# 32u4AVR.net
KiCad netlist of a schematic drawn in EAGLE
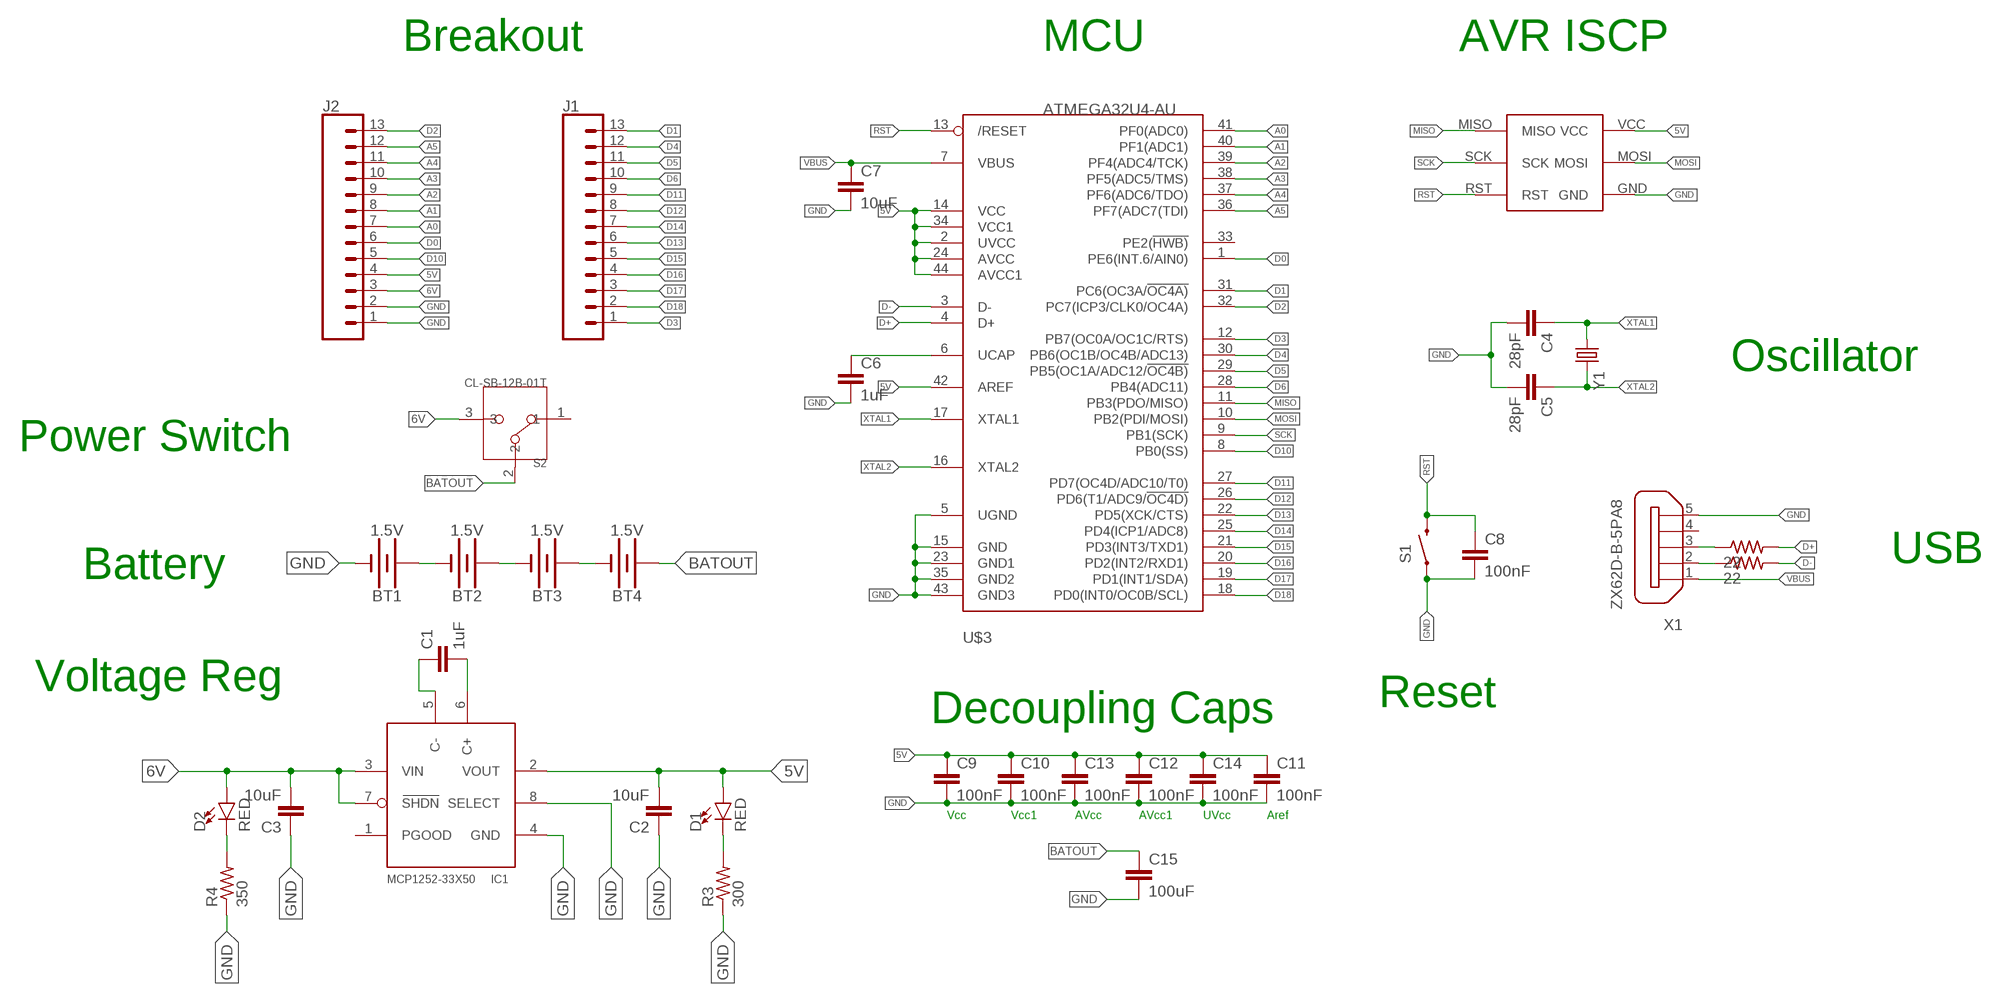
[diagram p0: schematic, sheet 1]

(export (version "E")
  (design (tool "Eeschema 10.0.6"))
  (components
    (comp (ref "BT1")
      (value "1.5V")
      (footprint "eagle-import:BATTERY-AA")
      (libsource (lib "eagle-import") (part "BATTERY-AA"))
    )
    (comp (ref "BT2")
      (value "1.5V")
      (footprint "eagle-import:BATTERY-AA")
      (libsource (lib "eagle-import") (part "BATTERY-AA"))
    )
    (comp (ref "BT3")
      (value "1.5V")
      (footprint "eagle-import:BATTERY-AA")
      (libsource (lib "eagle-import") (part "BATTERY-AA"))
    )
    (comp (ref "BT4")
      (value "1.5V")
      (footprint "eagle-import:BATTERY-AA")
      (libsource (lib "eagle-import") (part "BATTERY-AA"))
    )
    (comp (ref "C1")
      (value "1uF")
      (footprint "eagle-import:C0402K")
      (libsource (lib "eagle-import") (part "C-EUC0402K"))
    )
    (comp (ref "C2")
      (value "10uF")
      (footprint "eagle-import:C0402K")
      (libsource (lib "eagle-import") (part "C-EUC0402K"))
    )
    (comp (ref "C3")
      (value "10uF")
      (footprint "eagle-import:C0402K")
      (libsource (lib "eagle-import") (part "C-EUC0402K"))
    )
    (comp (ref "C4")
      (value "28pF")
      (footprint "eagle-import:C0402K")
      (libsource (lib "eagle-import") (part "C-EUC0402K"))
    )
    (comp (ref "C5")
      (value "28pF")
      (footprint "eagle-import:C0402K")
      (libsource (lib "eagle-import") (part "C-EUC0402K"))
    )
    (comp (ref "C6")
      (value "1uF")
      (footprint "eagle-import:C0402K")
      (libsource (lib "eagle-import") (part "C-EUC0402K"))
    )
    (comp (ref "C7")
      (value "10uF")
      (footprint "eagle-import:C0402K")
      (libsource (lib "eagle-import") (part "C-EUC0402K"))
    )
    (comp (ref "C8")
      (value "100nF")
      (footprint "eagle-import:C0402K")
      (libsource (lib "eagle-import") (part "C-EUC0402K"))
    )
    (comp (ref "C9")
      (value "100nF")
      (footprint "eagle-import:C0402K")
      (libsource (lib "eagle-import") (part "C-EUC0402K"))
    )
    (comp (ref "C10")
      (value "100nF")
      (footprint "eagle-import:C0402K")
      (libsource (lib "eagle-import") (part "C-EUC0402K"))
    )
    (comp (ref "C11")
      (value "100nF")
      (footprint "eagle-import:C0402K")
      (libsource (lib "eagle-import") (part "C-EUC0402K"))
    )
    (comp (ref "C12")
      (value "100nF")
      (footprint "eagle-import:C0402K")
      (libsource (lib "eagle-import") (part "C-EUC0402K"))
    )
    (comp (ref "C13")
      (value "100nF")
      (footprint "eagle-import:C0402K")
      (libsource (lib "eagle-import") (part "C-EUC0402K"))
    )
    (comp (ref "C14")
      (value "100nF")
      (footprint "eagle-import:C0402K")
      (libsource (lib "eagle-import") (part "C-EUC0402K"))
    )
    (comp (ref "C15")
      (value "100uF")
      (footprint "eagle-import:C1206K")
      (libsource (lib "eagle-import") (part "C-EUC1206K"))
    )
    (comp (ref "D1")
      (value "RED")
      (footprint "eagle-import:LED-0603")
      (libsource (lib "eagle-import") (part "LED-RED0603"))
    )
    (comp (ref "D2")
      (value "RED")
      (footprint "eagle-import:LED-0603")
      (libsource (lib "eagle-import") (part "LED-RED0603"))
    )
    (comp (ref "IC1")
      (value "MCP1252-33X50")
      (footprint "eagle-import:MSOP8")
      (libsource (lib "eagle-import") (part "MCP1252-33X50"))
    )
    (comp (ref "J1")
      (value "CONN_13LONGPADS")
      (footprint "eagle-import:1X13-LONGPADS")
      (libsource (lib "eagle-import") (part "CONN_13LONGPADS"))
    )
    (comp (ref "J2")
      (value "CONN_13LONGPADS")
      (footprint "eagle-import:1X13-LONGPADS")
      (libsource (lib "eagle-import") (part "CONN_13LONGPADS"))
    )
    (comp (ref "R3")
      (value "300")
      (footprint "eagle-import:R0402")
      (libsource (lib "eagle-import") (part "R-US_R0402"))
    )
    (comp (ref "R4")
      (value "350")
      (footprint "eagle-import:R0402")
      (libsource (lib "eagle-import") (part "R-US_R0402"))
    )
    (comp (ref "R5")
      (value "22")
      (footprint "eagle-import:R0402")
      (libsource (lib "eagle-import") (part "R-US_R0402"))
    )
    (comp (ref "R6")
      (value "22")
      (footprint "eagle-import:R0402")
      (libsource (lib "eagle-import") (part "R-US_R0402"))
    )
    (comp (ref "S1")
      (value "SWITCH-MOMENTARY-2SMD")
      (footprint "eagle-import:TACTILE-SWITCH-SMD")
      (libsource (lib "eagle-import") (part "SWITCH-MOMENTARY-2SMD"))
    )
    (comp (ref "S2")
      (value "CL-SB-12B-01T")
      (footprint "eagle-import:CL-SB-12B")
      (fields (field (name "MF") "Nidec Copal"))
      (libsource (lib "eagle-import") (part "CL-SB-12B-01T"))
    )
    (comp (ref "U$1")
      (value "AVR-ISP")
      (footprint "eagle-import:AVR-ISP")
      (fields (field (name "MF") "Gravitech"))
      (libsource (lib "eagle-import") (part "AVR-ISP"))
    )
    (comp (ref "U$3")
      (value "ATMEGA32U4-AU")
      (footprint "eagle-import:TQFP44")
      (libsource (lib "eagle-import") (part "ATMEGA32U4-AU"))
    )
    (comp (ref "X1")
      (value "ZX62D-B-5PA8")
      (footprint "eagle-import:ZX62D-B-5PA8")
      (fields (field (name "MF") "Hirose"))
      (libsource (lib "eagle-import") (part "ZX62D-B-5PA8"))
    )
    (comp (ref "Y1")
      (value "CRYSTALSMD")
      (footprint "eagle-import:HC49UP")
      (libsource (lib "eagle-import") (part "CRYSTALSMD"))
    )
  )
  (nets
    (net (code "1") (name "5V") (class "Default")
      (node (ref "C10") (pin "1") (pinfunction "1_1") (pintype "passive"))
      (node (ref "C11") (pin "1") (pinfunction "1_1") (pintype "passive"))
      (node (ref "C12") (pin "1") (pinfunction "1_1") (pintype "passive"))
      (node (ref "C13") (pin "1") (pinfunction "1_1") (pintype "passive"))
      (node (ref "C14") (pin "1") (pinfunction "1_1") (pintype "passive"))
      (node (ref "C2") (pin "2") (pinfunction "2_2") (pintype "passive"))
      (node (ref "C9") (pin "1") (pinfunction "1_1") (pintype "passive"))
      (node (ref "D1") (pin "A") (pinfunction "A_A") (pintype "passive"))
      (node (ref "IC1") (pin "2") (pinfunction "VOUT_2") (pintype "output"))
      (node (ref "J2") (pin "4") (pinfunction "4_4") (pintype "passive"))
      (node (ref "U$1") (pin "VCC") (pinfunction "VCC_VCC") (pintype "bidirectional"))
      (node (ref "U$3") (pin "14") (pinfunction "VCC_14") (pintype "bidirectional"))
      (node (ref "U$3") (pin "2") (pinfunction "UVCC_2") (pintype "bidirectional"))
      (node (ref "U$3") (pin "24") (pinfunction "AVCC_24") (pintype "bidirectional"))
      (node (ref "U$3") (pin "34") (pinfunction "VCC1_34") (pintype "bidirectional"))
      (node (ref "U$3") (pin "42") (pinfunction "AREF_42") (pintype "bidirectional"))
      (node (ref "U$3") (pin "44") (pinfunction "AVCC1_44") (pintype "bidirectional"))
    )
    (net (code "2") (name "6V") (class "Default")
      (node (ref "C3") (pin "2") (pinfunction "2_2") (pintype "passive"))
      (node (ref "D2") (pin "A") (pinfunction "A_A") (pintype "passive"))
      (node (ref "IC1") (pin "3") (pinfunction "VIN_3") (pintype "power_in"))
      (node (ref "IC1") (pin "7") (pinfunction "SHDN_7") (pintype "input"))
      (node (ref "J2") (pin "3") (pinfunction "3_3") (pintype "passive"))
      (node (ref "S2") (pin "3") (pinfunction "3_3") (pintype "bidirectional"))
    )
    (net (code "3") (name "A0") (class "Default")
      (node (ref "J2") (pin "7") (pinfunction "7_7") (pintype "passive"))
      (node (ref "U$3") (pin "41") (pinfunction "PF0(ADC0)_41") (pintype "bidirectional"))
    )
    (net (code "4") (name "A1") (class "Default")
      (node (ref "J2") (pin "8") (pinfunction "8_8") (pintype "passive"))
      (node (ref "U$3") (pin "40") (pinfunction "PF1(ADC1)_40") (pintype "bidirectional"))
    )
    (net (code "5") (name "A2") (class "Default")
      (node (ref "J2") (pin "9") (pinfunction "9_9") (pintype "passive"))
      (node (ref "U$3") (pin "39") (pinfunction "PF4(ADC4/TCK)_39") (pintype "bidirectional"))
    )
    (net (code "6") (name "A3") (class "Default")
      (node (ref "J2") (pin "10") (pinfunction "10_10") (pintype "passive"))
      (node (ref "U$3") (pin "38") (pinfunction "PF5(ADC5/TMS)_38") (pintype "bidirectional"))
    )
    (net (code "7") (name "A4") (class "Default")
      (node (ref "J2") (pin "11") (pinfunction "11_11") (pintype "passive"))
      (node (ref "U$3") (pin "37") (pinfunction "PF6(ADC6/TDO)_37") (pintype "bidirectional"))
    )
    (net (code "8") (name "A5") (class "Default")
      (node (ref "J2") (pin "12") (pinfunction "12_12") (pintype "passive"))
      (node (ref "U$3") (pin "36") (pinfunction "PF7(ADC7(TDI)_36") (pintype "bidirectional"))
    )
    (net (code "9") (name "BATOUT") (class "Default")
      (node (ref "BT4") (pin "PWR@1") (pinfunction "+_PWR@1") (pintype "power_in"))
      (node (ref "C15") (pin "1") (pinfunction "1_1") (pintype "passive"))
      (node (ref "S2") (pin "2") (pinfunction "2_2") (pintype "bidirectional"))
    )
    (net (code "10") (name "D+") (class "Default")
      (node (ref "R5") (pin "2") (pinfunction "2_2") (pintype "passive"))
      (node (ref "U$3") (pin "4") (pinfunction "D+_4") (pintype "bidirectional"))
    )
    (net (code "11") (name "D-") (class "Default")
      (node (ref "R6") (pin "2") (pinfunction "2_2") (pintype "passive"))
      (node (ref "U$3") (pin "3") (pinfunction "D-_3") (pintype "bidirectional"))
    )
    (net (code "12") (name "D0") (class "Default")
      (node (ref "J2") (pin "6") (pinfunction "6_6") (pintype "passive"))
      (node (ref "U$3") (pin "1") (pinfunction "PE6(INT.6/AIN0)_1") (pintype "bidirectional"))
    )
    (net (code "13") (name "D1") (class "Default")
      (node (ref "J1") (pin "13") (pinfunction "13_13") (pintype "passive"))
      (node (ref "U$3") (pin "31") (pinfunction "PC6(OC3A/~{OC4A})_31") (pintype "bidirectional"))
    )
    (net (code "14") (name "D2") (class "Default")
      (node (ref "J2") (pin "13") (pinfunction "13_13") (pintype "passive"))
      (node (ref "U$3") (pin "32") (pinfunction "PC7(ICP3/CLK0/OC4A)_32") (pintype "bidirectional"))
    )
    (net (code "15") (name "D3") (class "Default")
      (node (ref "J1") (pin "1") (pinfunction "1_1") (pintype "passive"))
      (node (ref "U$3") (pin "12") (pinfunction "PB7(OC0A/OC1C/RTS)_12") (pintype "bidirectional"))
    )
    (net (code "16") (name "D4") (class "Default")
      (node (ref "J1") (pin "12") (pinfunction "12_12") (pintype "passive"))
      (node (ref "U$3") (pin "30") (pinfunction "PB6(OC1B/OC4B/ADC13)_30") (pintype "bidirectional"))
    )
    (net (code "17") (name "D5") (class "Default")
      (node (ref "J1") (pin "11") (pinfunction "11_11") (pintype "passive"))
      (node (ref "U$3") (pin "29") (pinfunction "PB5(OC1A/ADC12/~{OC4B})_29") (pintype "bidirectional"))
    )
    (net (code "18") (name "D6") (class "Default")
      (node (ref "J1") (pin "10") (pinfunction "10_10") (pintype "passive"))
      (node (ref "U$3") (pin "28") (pinfunction "PB4(ADC11)_28") (pintype "bidirectional"))
    )
    (net (code "19") (name "D10") (class "Default")
      (node (ref "J2") (pin "5") (pinfunction "5_5") (pintype "passive"))
      (node (ref "U$3") (pin "8") (pinfunction "PB0(SS)_8") (pintype "bidirectional"))
    )
    (net (code "20") (name "D11") (class "Default")
      (node (ref "J1") (pin "9") (pinfunction "9_9") (pintype "passive"))
      (node (ref "U$3") (pin "27") (pinfunction "PD7(OC4D/ADC10/T0)_27") (pintype "bidirectional"))
    )
    (net (code "21") (name "D12") (class "Default")
      (node (ref "J1") (pin "8") (pinfunction "8_8") (pintype "passive"))
      (node (ref "U$3") (pin "26") (pinfunction "PD6(T1/ADC9/~{OC4D})_26") (pintype "bidirectional"))
    )
    (net (code "22") (name "D13") (class "Default")
      (node (ref "J1") (pin "6") (pinfunction "6_6") (pintype "passive"))
      (node (ref "U$3") (pin "22") (pinfunction "PD5(XCK/CTS)_22") (pintype "bidirectional"))
    )
    (net (code "23") (name "D14") (class "Default")
      (node (ref "J1") (pin "7") (pinfunction "7_7") (pintype "passive"))
      (node (ref "U$3") (pin "25") (pinfunction "PD4(ICP1/ADC8)_25") (pintype "bidirectional"))
    )
    (net (code "24") (name "D15") (class "Default")
      (node (ref "J1") (pin "5") (pinfunction "5_5") (pintype "passive"))
      (node (ref "U$3") (pin "21") (pinfunction "PD3(INT3/TXD1)_21") (pintype "bidirectional"))
    )
    (net (code "25") (name "D16") (class "Default")
      (node (ref "J1") (pin "4") (pinfunction "4_4") (pintype "passive"))
      (node (ref "U$3") (pin "20") (pinfunction "PD2(INT2/RXD1)_20") (pintype "bidirectional"))
    )
    (net (code "26") (name "D17") (class "Default")
      (node (ref "J1") (pin "3") (pinfunction "3_3") (pintype "passive"))
      (node (ref "U$3") (pin "19") (pinfunction "PD1(INT1/SDA)_19") (pintype "bidirectional"))
    )
    (net (code "27") (name "D18") (class "Default")
      (node (ref "J1") (pin "2") (pinfunction "2_2") (pintype "passive"))
      (node (ref "U$3") (pin "18") (pinfunction "PD0(INT0/OC0B/SCL)_18") (pintype "bidirectional"))
    )
    (net (code "28") (name "GND") (class "Default")
      (node (ref "BT1") (pin "GND@1") (pinfunction "-_GND@1") (pintype "power_in"))
      (node (ref "C10") (pin "2") (pinfunction "2_2") (pintype "passive"))
      (node (ref "C11") (pin "2") (pinfunction "2_2") (pintype "passive"))
      (node (ref "C12") (pin "2") (pinfunction "2_2") (pintype "passive"))
      (node (ref "C13") (pin "2") (pinfunction "2_2") (pintype "passive"))
      (node (ref "C14") (pin "2") (pinfunction "2_2") (pintype "passive"))
      (node (ref "C15") (pin "2") (pinfunction "2_2") (pintype "passive"))
      (node (ref "C2") (pin "1") (pinfunction "1_1") (pintype "passive"))
      (node (ref "C3") (pin "1") (pinfunction "1_1") (pintype "passive"))
      (node (ref "C4") (pin "2") (pinfunction "2_2") (pintype "passive"))
      (node (ref "C5") (pin "2") (pinfunction "2_2") (pintype "passive"))
      (node (ref "C6") (pin "2") (pinfunction "2_2") (pintype "passive"))
      (node (ref "C7") (pin "2") (pinfunction "2_2") (pintype "passive"))
      (node (ref "C8") (pin "2") (pinfunction "2_2") (pintype "passive"))
      (node (ref "C9") (pin "2") (pinfunction "2_2") (pintype "passive"))
      (node (ref "IC1") (pin "4") (pinfunction "GND_4") (pintype "power_in"))
      (node (ref "IC1") (pin "8") (pinfunction "SELECT_8") (pintype "input"))
      (node (ref "J2") (pin "1") (pinfunction "1_1") (pintype "passive"))
      (node (ref "J2") (pin "2") (pinfunction "2_2") (pintype "passive"))
      (node (ref "R3") (pin "1") (pinfunction "1_1") (pintype "passive"))
      (node (ref "R4") (pin "1") (pinfunction "1_1") (pintype "passive"))
      (node (ref "S1") (pin "1") (pinfunction "1_1") (pintype "passive"))
      (node (ref "U$1") (pin "GND") (pinfunction "GND_GND") (pintype "bidirectional"))
      (node (ref "U$3") (pin "15") (pinfunction "GND_15") (pintype "bidirectional"))
      (node (ref "U$3") (pin "23") (pinfunction "GND1_23") (pintype "bidirectional"))
      (node (ref "U$3") (pin "35") (pinfunction "GND2_35") (pintype "bidirectional"))
      (node (ref "U$3") (pin "43") (pinfunction "GND3_43") (pintype "bidirectional"))
      (node (ref "U$3") (pin "5") (pinfunction "UGND_5") (pintype "bidirectional"))
      (node (ref "X1") (pin "5") (pinfunction "5_5") (pintype "passive"))
    )
    (net (code "29") (name "MISO") (class "Default")
      (node (ref "U$1") (pin "MISO") (pinfunction "MISO_MISO") (pintype "bidirectional"))
      (node (ref "U$3") (pin "11") (pinfunction "PB3(PDO/MISO)_11") (pintype "bidirectional"))
    )
    (net (code "30") (name "MOSI") (class "Default")
      (node (ref "U$1") (pin "MOSI") (pinfunction "MOSI_MOSI") (pintype "bidirectional"))
      (node (ref "U$3") (pin "10") (pinfunction "PB2(PDI/MOSI)_10") (pintype "bidirectional"))
    )
    (net (code "31") (name "Net-(BT1-+)") (class "Default")
      (node (ref "BT1") (pin "PWR@1") (pinfunction "+_PWR@1") (pintype "power_in"))
      (node (ref "BT2") (pin "GND@1") (pinfunction "-_GND@1") (pintype "power_in"))
    )
    (net (code "32") (name "Net-(BT2-+)") (class "Default")
      (node (ref "BT2") (pin "PWR@1") (pinfunction "+_PWR@1") (pintype "power_in"))
      (node (ref "BT3") (pin "GND@1") (pinfunction "-_GND@1") (pintype "power_in"))
    )
    (net (code "33") (name "Net-(BT3-+)") (class "Default")
      (node (ref "BT3") (pin "PWR@1") (pinfunction "+_PWR@1") (pintype "power_in"))
      (node (ref "BT4") (pin "GND@1") (pinfunction "-_GND@1") (pintype "power_in"))
    )
    (net (code "34") (name "Net-(D1-PadC)") (class "Default")
      (node (ref "D1") (pin "C") (pinfunction "C_C") (pintype "passive"))
      (node (ref "R3") (pin "2") (pinfunction "2_2") (pintype "passive"))
    )
    (net (code "35") (name "Net-(D2-PadC)") (class "Default")
      (node (ref "D2") (pin "C") (pinfunction "C_C") (pintype "passive"))
      (node (ref "R4") (pin "2") (pinfunction "2_2") (pintype "passive"))
    )
    (net (code "36") (name "Net-(IC1-C+)") (class "Default")
      (node (ref "C1") (pin "2") (pinfunction "2_2") (pintype "passive"))
      (node (ref "IC1") (pin "6") (pinfunction "C+_6") (pintype "passive"))
    )
    (net (code "37") (name "Net-(IC1-C-)") (class "Default")
      (node (ref "C1") (pin "1") (pinfunction "1_1") (pintype "passive"))
      (node (ref "IC1") (pin "5") (pinfunction "C-_5") (pintype "passive"))
    )
    (net (code "38") (name "Net-(R5-Pad1)") (class "Default")
      (node (ref "R5") (pin "1") (pinfunction "1_1") (pintype "passive"))
      (node (ref "X1") (pin "3") (pinfunction "3_3") (pintype "passive"))
    )
    (net (code "39") (name "Net-(R6-Pad1)") (class "Default")
      (node (ref "R6") (pin "1") (pinfunction "1_1") (pintype "passive"))
      (node (ref "X1") (pin "2") (pinfunction "2_2") (pintype "passive"))
    )
    (net (code "40") (name "Net-(U$3-UCAP)") (class "Default")
      (node (ref "C6") (pin "1") (pinfunction "1_1") (pintype "passive"))
      (node (ref "U$3") (pin "6") (pinfunction "UCAP_6") (pintype "bidirectional"))
    )
    (net (code "41") (name "RST") (class "Default")
      (node (ref "C8") (pin "1") (pinfunction "1_1") (pintype "passive"))
      (node (ref "S1") (pin "3") (pinfunction "2_3") (pintype "passive"))
      (node (ref "U$1") (pin "RST") (pinfunction "RST_RST") (pintype "bidirectional"))
      (node (ref "U$3") (pin "13") (pinfunction "/RESET_13") (pintype "bidirectional"))
    )
    (net (code "42") (name "SCK") (class "Default")
      (node (ref "U$1") (pin "SCK") (pinfunction "SCK_SCK") (pintype "bidirectional"))
      (node (ref "U$3") (pin "9") (pinfunction "PB1(SCK)_9") (pintype "bidirectional"))
    )
    (net (code "43") (name "VBUS") (class "Default")
      (node (ref "C7") (pin "1") (pinfunction "1_1") (pintype "passive"))
      (node (ref "U$3") (pin "7") (pinfunction "VBUS_7") (pintype "bidirectional"))
      (node (ref "X1") (pin "1") (pinfunction "1_1") (pintype "passive"))
    )
    (net (code "44") (name "XTAL1") (class "Default")
      (node (ref "C4") (pin "1") (pinfunction "1_1") (pintype "passive"))
      (node (ref "U$3") (pin "17") (pinfunction "XTAL1_17") (pintype "bidirectional"))
      (node (ref "Y1") (pin "1") (pinfunction "1_1") (pintype "passive"))
    )
    (net (code "45") (name "XTAL2") (class "Default")
      (node (ref "C5") (pin "1") (pinfunction "1_1") (pintype "passive"))
      (node (ref "U$3") (pin "16") (pinfunction "XTAL2_16") (pintype "bidirectional"))
      (node (ref "Y1") (pin "2") (pinfunction "2_2") (pintype "passive"))
    )
    (net (code "46") (name "unconnected-(IC1-PGOOD-Pad1)") (class "Default")
      (node (ref "IC1") (pin "1") (pinfunction "PGOOD_1") (pintype "output"))
    )
    (net (code "47") (name "unconnected-(S2-Pad1)") (class "Default")
      (node (ref "S2") (pin "1") (pinfunction "1_1") (pintype "bidirectional"))
    )
    (net (code "48") (name "unconnected-(U$3-PE2(~{HWB})-Pad33)") (class "Default")
      (node (ref "U$3") (pin "33") (pinfunction "PE2(~{HWB})_33") (pintype "bidirectional"))
    )
    (net (code "49") (name "unconnected-(X1-Pad4)") (class "Default")
      (node (ref "X1") (pin "4") (pinfunction "4_4") (pintype "passive"))
    )
  )
)
